# ce3.net
KiCad netlist of a schematic drawn in EAGLE
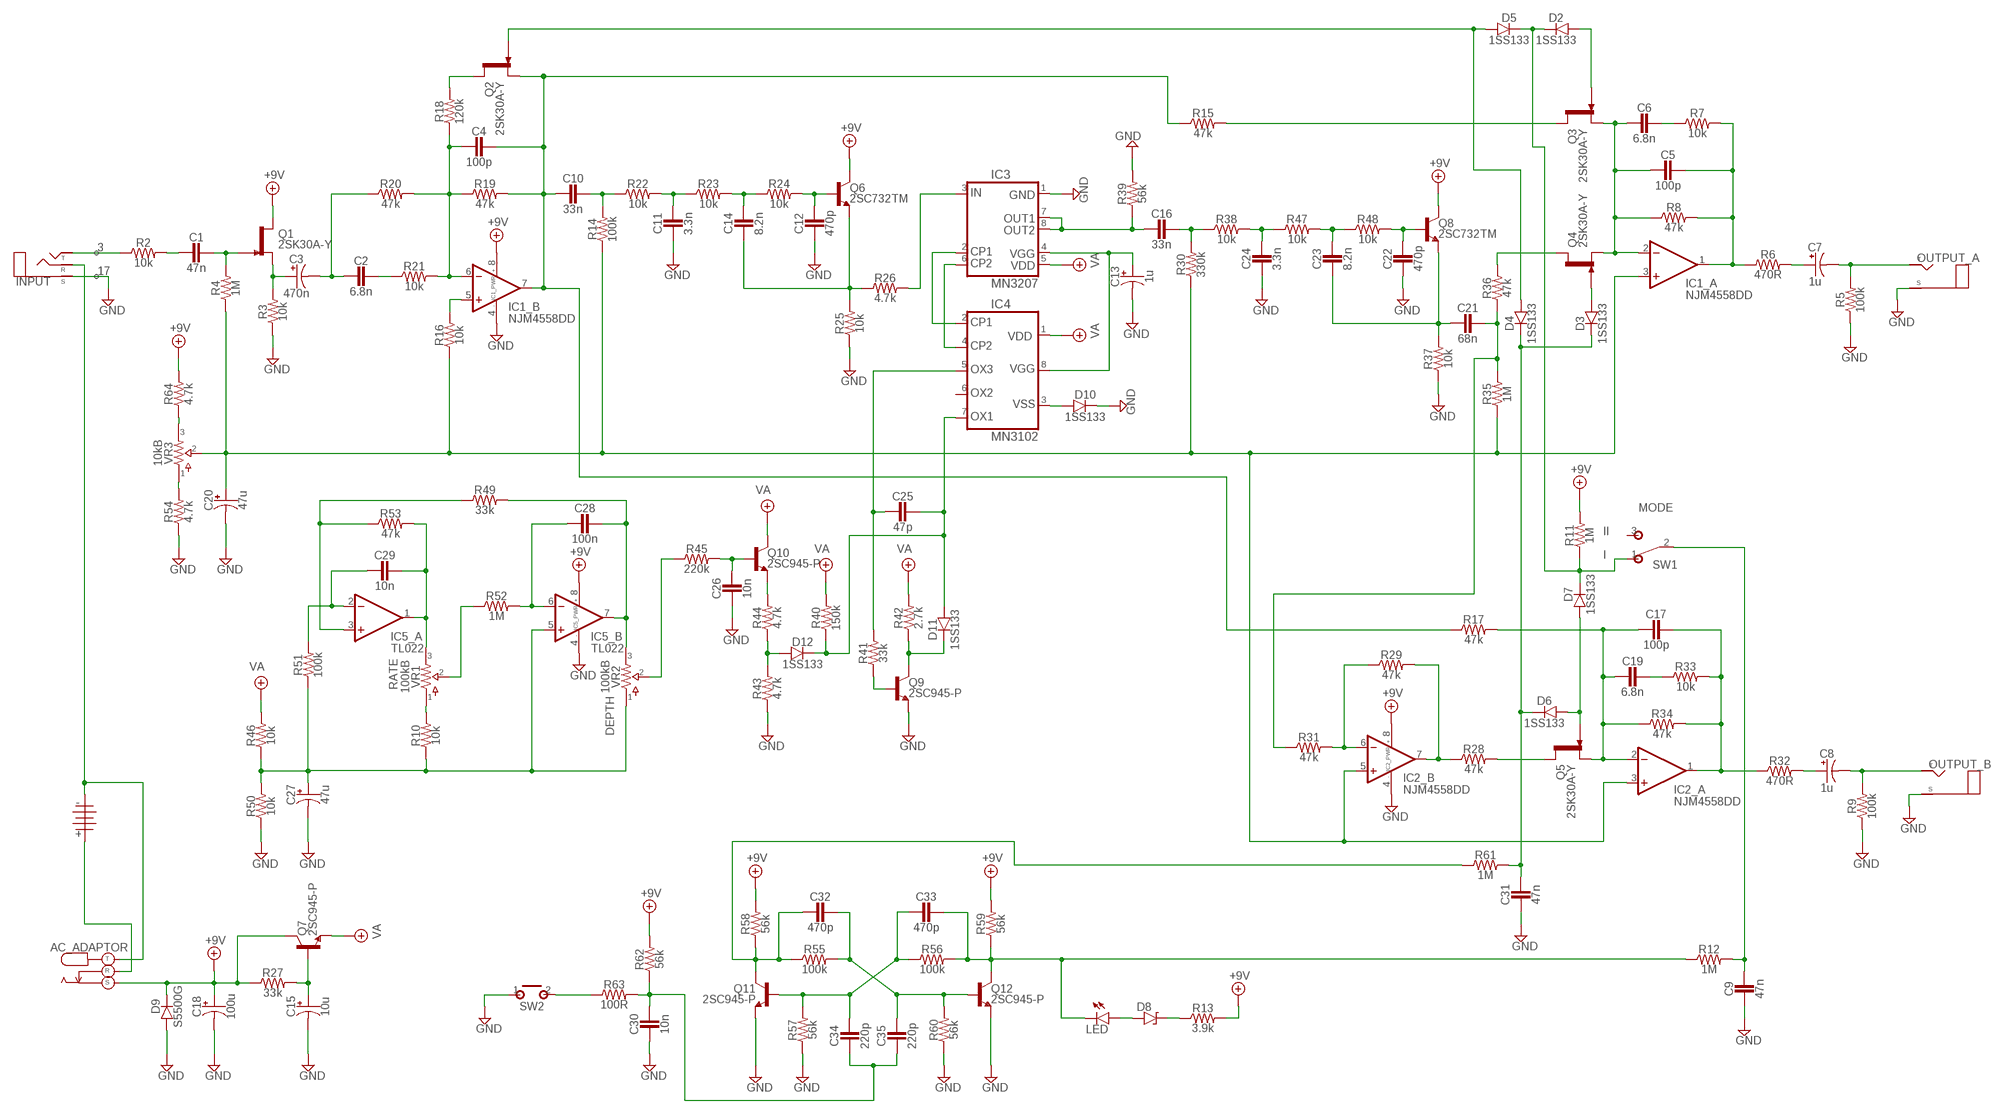
[diagram p0: schematic, sheet 1]

(export (version "E")
  (design (tool "Eeschema 10.0.6"))
  (components
    (comp (ref "1101")
      (value "BATTERY")
      (footprint "eagle-import:TWO_PADS")
      (libsource (lib "eagle-import") (part "BATTERY"))
    )
    (comp (ref "AC_ADAPTOR")
      (value "DC_KOBICONN")
      (footprint "eagle-import:DC_KOBICONN")
      (libsource (lib "eagle-import") (part "DC_KOBICONN"))
    )
    (comp (ref "C1")
      (value "47n")
      (footprint "eagle-import:BOX_SMALL")
      (libsource (lib "eagle-import") (part "CER/FILMBOX.1"))
    )
    (comp (ref "C2")
      (value "6.8n")
      (footprint "eagle-import:BOX_SMALL")
      (libsource (lib "eagle-import") (part "CER/FILMBOX.1"))
    )
    (comp (ref "C3")
      (value "470n")
      (footprint "eagle-import:040_020")
      (libsource (lib "eagle-import") (part "0400"))
    )
    (comp (ref "C4")
      (value "100p")
      (footprint "eagle-import:BOX_SMALL")
      (libsource (lib "eagle-import") (part "CER/FILMBOX.1"))
    )
    (comp (ref "C5")
      (value "100p")
      (footprint "eagle-import:BOX_SMALL")
      (libsource (lib "eagle-import") (part "CER/FILMBOX.1"))
    )
    (comp (ref "C6")
      (value "6.8n")
      (footprint "eagle-import:BOX_SMALL")
      (libsource (lib "eagle-import") (part "CER/FILMBOX.1"))
    )
    (comp (ref "C7")
      (value "1u")
      (footprint "eagle-import:040_020")
      (libsource (lib "eagle-import") (part "0400"))
    )
    (comp (ref "C8")
      (value "1u")
      (footprint "eagle-import:040_020")
      (libsource (lib "eagle-import") (part "0400"))
    )
    (comp (ref "C9")
      (value "47n")
      (footprint "eagle-import:BOX_SMALL")
      (libsource (lib "eagle-import") (part "CER/FILMBOX.1"))
    )
    (comp (ref "C10")
      (value "33n")
      (footprint "eagle-import:BOX_SMALL")
      (libsource (lib "eagle-import") (part "CER/FILMBOX.1"))
    )
    (comp (ref "C11")
      (value "3.3n")
      (footprint "eagle-import:BOX_SMALL")
      (libsource (lib "eagle-import") (part "CER/FILMBOX.1"))
    )
    (comp (ref "C12")
      (value "470p")
      (footprint "eagle-import:BOX_SMALL")
      (libsource (lib "eagle-import") (part "CER/FILMBOX.1"))
    )
    (comp (ref "C13")
      (value "1u")
      (footprint "eagle-import:040_020")
      (libsource (lib "eagle-import") (part "0400"))
    )
    (comp (ref "C14")
      (value "8.2n")
      (footprint "eagle-import:BOX_SMALL")
      (libsource (lib "eagle-import") (part "CER/FILMBOX.1"))
    )
    (comp (ref "C15")
      (value "10u")
      (footprint "eagle-import:040_020")
      (libsource (lib "eagle-import") (part "0400"))
    )
    (comp (ref "C16")
      (value "33n")
      (footprint "eagle-import:BOX_SMALL")
      (libsource (lib "eagle-import") (part "CER/FILMBOX.1"))
    )
    (comp (ref "C17")
      (value "100p")
      (footprint "eagle-import:BOX_SMALL")
      (libsource (lib "eagle-import") (part "CER/FILMBOX.1"))
    )
    (comp (ref "C18")
      (value "100u")
      (footprint "eagle-import:040_020")
      (libsource (lib "eagle-import") (part "0400"))
    )
    (comp (ref "C19")
      (value "6.8n")
      (footprint "eagle-import:BOX_SMALL")
      (libsource (lib "eagle-import") (part "CER/FILMBOX.1"))
    )
    (comp (ref "C20")
      (value "47u")
      (footprint "eagle-import:040_020")
      (libsource (lib "eagle-import") (part "0400"))
    )
    (comp (ref "C21")
      (value "68n")
      (footprint "eagle-import:BOX_SMALL")
      (libsource (lib "eagle-import") (part "CER/FILMBOX.1"))
    )
    (comp (ref "C22")
      (value "470p")
      (footprint "eagle-import:BOX_SMALL")
      (libsource (lib "eagle-import") (part "CER/FILMBOX.1"))
    )
    (comp (ref "C23")
      (value "8.2n")
      (footprint "eagle-import:BOX_SMALL")
      (libsource (lib "eagle-import") (part "CER/FILMBOX.1"))
    )
    (comp (ref "C24")
      (value "3.3n")
      (footprint "eagle-import:BOX_SMALL")
      (libsource (lib "eagle-import") (part "CER/FILMBOX.1"))
    )
    (comp (ref "C25")
      (value "47p")
      (footprint "eagle-import:BOX_SMALL")
      (libsource (lib "eagle-import") (part "CER/FILMBOX.1"))
    )
    (comp (ref "C26")
      (value "10n")
      (footprint "eagle-import:BOX_SMALL")
      (libsource (lib "eagle-import") (part "CER/FILMBOX.1"))
    )
    (comp (ref "C27")
      (value "47u")
      (footprint "eagle-import:040_020")
      (libsource (lib "eagle-import") (part "0400"))
    )
    (comp (ref "C28")
      (value "100n")
      (footprint "eagle-import:BOX_SMALL")
      (libsource (lib "eagle-import") (part "CER/FILMBOX.1"))
    )
    (comp (ref "C29")
      (value "10n")
      (footprint "eagle-import:BOX_SMALL")
      (libsource (lib "eagle-import") (part "CER/FILMBOX.1"))
    )
    (comp (ref "C30")
      (value "10n")
      (footprint "eagle-import:BOX_SMALL")
      (libsource (lib "eagle-import") (part "CER/FILMBOX.1"))
    )
    (comp (ref "C31")
      (value "47n")
      (footprint "eagle-import:BOX_SMALL")
      (libsource (lib "eagle-import") (part "CER/FILMBOX.1"))
    )
    (comp (ref "C32")
      (value "470p")
      (footprint "eagle-import:BOX_SMALL")
      (libsource (lib "eagle-import") (part "CER/FILMBOX.1"))
    )
    (comp (ref "C33")
      (value "470p")
      (footprint "eagle-import:BOX_SMALL")
      (libsource (lib "eagle-import") (part "CER/FILMBOX.1"))
    )
    (comp (ref "C34")
      (value "220p")
      (footprint "eagle-import:BOX_SMALL")
      (libsource (lib "eagle-import") (part "CER/FILMBOX.1"))
    )
    (comp (ref "C35")
      (value "220p")
      (footprint "eagle-import:BOX_SMALL")
      (libsource (lib "eagle-import") (part "CER/FILMBOX.1"))
    )
    (comp (ref "D2")
      (value "1SS133")
      (footprint "eagle-import:DO35-2")
      (libsource (lib "eagle-import") (part "DO35.2"))
    )
    (comp (ref "D3")
      (value "1SS133")
      (footprint "eagle-import:DO35-2")
      (libsource (lib "eagle-import") (part "DO35.2"))
    )
    (comp (ref "D4")
      (value "1SS133")
      (footprint "eagle-import:DO35-2")
      (libsource (lib "eagle-import") (part "DO35.2"))
    )
    (comp (ref "D5")
      (value "1SS133")
      (footprint "eagle-import:DO35-2")
      (libsource (lib "eagle-import") (part "DO35.2"))
    )
    (comp (ref "D6")
      (value "1SS133")
      (footprint "eagle-import:DO35-2")
      (libsource (lib "eagle-import") (part "DO35.2"))
    )
    (comp (ref "D7")
      (value "1SS133")
      (footprint "eagle-import:DO35-2")
      (libsource (lib "eagle-import") (part "DO35.2"))
    )
    (comp (ref "D8")
      (value "ZENER.2")
      (footprint "eagle-import:DO41-2")
      (libsource (lib "eagle-import") (part "ZENER.2"))
    )
    (comp (ref "D9")
      (value "S5500G")
      (footprint "eagle-import:DO35-2")
      (libsource (lib "eagle-import") (part "DO35.2"))
    )
    (comp (ref "D10")
      (value "1SS133")
      (footprint "eagle-import:DO35-2")
      (libsource (lib "eagle-import") (part "DO35.2"))
    )
    (comp (ref "D11")
      (value "1SS133")
      (footprint "eagle-import:DO35-2")
      (libsource (lib "eagle-import") (part "DO35.2"))
    )
    (comp (ref "D12")
      (value "1SS133")
      (footprint "eagle-import:DO35-2")
      (libsource (lib "eagle-import") (part "DO35.2"))
    )
    (comp (ref "IC1")
      (value "NJM4558DD")
      (footprint "eagle-import:DIL0")
      (libsource (lib "eagle-import") (part "DUALTH"))
    )
    (comp (ref "IC2")
      (value "NJM4558DD")
      (footprint "eagle-import:DIL0")
      (libsource (lib "eagle-import") (part "DUALTH"))
    )
    (comp (ref "IC3")
      (value "MN3207")
      (footprint "eagle-import:DIL0")
      (libsource (lib "eagle-import") (part "BL3208"))
    )
    (comp (ref "IC4")
      (value "MN3102")
      (footprint "eagle-import:DIL8")
      (libsource (lib "eagle-import") (part "CLOCK"))
    )
    (comp (ref "IC5")
      (value "TL022")
      (footprint "eagle-import:DIL0")
      (libsource (lib "eagle-import") (part "DUALTH"))
    )
    (comp (ref "INPUT")
      (value "STEREO3PADS")
      (footprint "eagle-import:THREEPADS")
      (libsource (lib "eagle-import") (part "STEREO3PADS"))
    )
    (comp (ref "LED")
      (value "LED")
      (footprint "eagle-import:3MM_D")
      (libsource (lib "eagle-import") (part "LED"))
    )
    (comp (ref "OUTPUT_A")
      (value "MONO")
      (footprint "eagle-import:TWO_PADS")
      (libsource (lib "eagle-import") (part "MONO"))
    )
    (comp (ref "OUTPUT_B")
      (value "MONO")
      (footprint "eagle-import:TWO_PADS")
      (libsource (lib "eagle-import") (part "MONO"))
    )
    (comp (ref "Q1")
      (value "2SK30A-Y")
      (footprint "eagle-import:TO92-")
      (libsource (lib "eagle-import") (part "2N5457"))
    )
    (comp (ref "Q2")
      (value "2SK30A-Y")
      (footprint "eagle-import:TO92-")
      (libsource (lib "eagle-import") (part "2N5457"))
    )
    (comp (ref "Q3")
      (value "2SK30A-Y")
      (footprint "eagle-import:TO92-")
      (libsource (lib "eagle-import") (part "2N5457"))
    )
    (comp (ref "Q4")
      (value "2SK30A-Y")
      (footprint "eagle-import:TO92-")
      (libsource (lib "eagle-import") (part "2N5457"))
    )
    (comp (ref "Q5")
      (value "2SK30A-Y")
      (footprint "eagle-import:TO92-")
      (libsource (lib "eagle-import") (part "2N5457"))
    )
    (comp (ref "Q6")
      (value "2SC732TM")
      (footprint "eagle-import:TO92-")
      (libsource (lib "eagle-import") (part "2SC828A"))
    )
    (comp (ref "Q7")
      (value "2SC945-P")
      (footprint "eagle-import:TO92-")
      (libsource (lib "eagle-import") (part "2SC828A"))
    )
    (comp (ref "Q8")
      (value "2SC732TM")
      (footprint "eagle-import:TO92-")
      (libsource (lib "eagle-import") (part "2SC828A"))
    )
    (comp (ref "Q9")
      (value "2SC945-P")
      (footprint "eagle-import:TO92-")
      (libsource (lib "eagle-import") (part "2SC828A"))
    )
    (comp (ref "Q10")
      (value "2SC945-P")
      (footprint "eagle-import:TO92-")
      (libsource (lib "eagle-import") (part "2SC828A"))
    )
    (comp (ref "Q11")
      (value "2SC945-P")
      (footprint "eagle-import:TO92-")
      (libsource (lib "eagle-import") (part "2SC828A"))
    )
    (comp (ref "Q12")
      (value "2SC945-P")
      (footprint "eagle-import:TO92-")
      (libsource (lib "eagle-import") (part "2SC828A"))
    )
    (comp (ref "R2")
      (value "10k")
      (footprint "eagle-import:R0207_3")
      (libsource (lib "eagle-import") (part "R_.3B"))
    )
    (comp (ref "R3")
      (value "10k")
      (footprint "eagle-import:R0207_3")
      (libsource (lib "eagle-import") (part "R_.3B"))
    )
    (comp (ref "R4")
      (value "1M")
      (footprint "eagle-import:R0207_3")
      (libsource (lib "eagle-import") (part "R_.3B"))
    )
    (comp (ref "R5")
      (value "100k")
      (footprint "eagle-import:R0207_3")
      (libsource (lib "eagle-import") (part "R_.3B"))
    )
    (comp (ref "R6")
      (value "470R")
      (footprint "eagle-import:R0207_3")
      (libsource (lib "eagle-import") (part "R_.3B"))
    )
    (comp (ref "R7")
      (value "10k")
      (footprint "eagle-import:R0207_3")
      (libsource (lib "eagle-import") (part "R_.3B"))
    )
    (comp (ref "R8")
      (value "47k")
      (footprint "eagle-import:R0207_3")
      (libsource (lib "eagle-import") (part "R_.3B"))
    )
    (comp (ref "R9")
      (value "100k")
      (footprint "eagle-import:R0207_3")
      (libsource (lib "eagle-import") (part "R_.3B"))
    )
    (comp (ref "R10")
      (value "10k")
      (footprint "eagle-import:R0207_3")
      (libsource (lib "eagle-import") (part "R_.3B"))
    )
    (comp (ref "R11")
      (value "1M")
      (footprint "eagle-import:R0207_3")
      (libsource (lib "eagle-import") (part "R_.3B"))
    )
    (comp (ref "R12")
      (value "1M")
      (footprint "eagle-import:R0207_3")
      (libsource (lib "eagle-import") (part "R_.3B"))
    )
    (comp (ref "R13")
      (value "3.9k")
      (footprint "eagle-import:R0207_3")
      (libsource (lib "eagle-import") (part "R_.3B"))
    )
    (comp (ref "R14")
      (value "100k")
      (footprint "eagle-import:R0207_3")
      (libsource (lib "eagle-import") (part "R_.3B"))
    )
    (comp (ref "R15")
      (value "47k")
      (footprint "eagle-import:R0207_3")
      (libsource (lib "eagle-import") (part "R_.3B"))
    )
    (comp (ref "R16")
      (value "10k")
      (footprint "eagle-import:R0207_3")
      (libsource (lib "eagle-import") (part "R_.3B"))
    )
    (comp (ref "R17")
      (value "47k")
      (footprint "eagle-import:R0207_3")
      (libsource (lib "eagle-import") (part "R_.3B"))
    )
    (comp (ref "R18")
      (value "120k")
      (footprint "eagle-import:R0207_3")
      (libsource (lib "eagle-import") (part "R_.3B"))
    )
    (comp (ref "R19")
      (value "47k")
      (footprint "eagle-import:R0207_3")
      (libsource (lib "eagle-import") (part "R_.3B"))
    )
    (comp (ref "R20")
      (value "47k")
      (footprint "eagle-import:R0207_3")
      (libsource (lib "eagle-import") (part "R_.3B"))
    )
    (comp (ref "R21")
      (value "10k")
      (footprint "eagle-import:R0207_3")
      (libsource (lib "eagle-import") (part "R_.3B"))
    )
    (comp (ref "R22")
      (value "10k")
      (footprint "eagle-import:R0207_3")
      (libsource (lib "eagle-import") (part "R_.3B"))
    )
    (comp (ref "R23")
      (value "10k")
      (footprint "eagle-import:R0207_3")
      (libsource (lib "eagle-import") (part "R_.3B"))
    )
    (comp (ref "R24")
      (value "10k")
      (footprint "eagle-import:R0207_3")
      (libsource (lib "eagle-import") (part "R_.3B"))
    )
    (comp (ref "R25")
      (value "10k")
      (footprint "eagle-import:R0207_3")
      (libsource (lib "eagle-import") (part "R_.3B"))
    )
    (comp (ref "R26")
      (value "4.7k")
      (footprint "eagle-import:R0207_3")
      (libsource (lib "eagle-import") (part "R_.3B"))
    )
    (comp (ref "R27")
      (value "33k")
      (footprint "eagle-import:R0207_3")
      (libsource (lib "eagle-import") (part "R_.3B"))
    )
    (comp (ref "R28")
      (value "47k")
      (footprint "eagle-import:R0207_3")
      (libsource (lib "eagle-import") (part "R_.3B"))
    )
    (comp (ref "R29")
      (value "47k")
      (footprint "eagle-import:R0207_3")
      (libsource (lib "eagle-import") (part "R_.3B"))
    )
    (comp (ref "R30")
      (value "330k")
      (footprint "eagle-import:R0207_3")
      (libsource (lib "eagle-import") (part "R_.3B"))
    )
    (comp (ref "R31")
      (value "47k")
      (footprint "eagle-import:R0207_3")
      (libsource (lib "eagle-import") (part "R_.3B"))
    )
    (comp (ref "R32")
      (value "470R")
      (footprint "eagle-import:R0207_3")
      (libsource (lib "eagle-import") (part "R_.3B"))
    )
    (comp (ref "R33")
      (value "10k")
      (footprint "eagle-import:R0207_3")
      (libsource (lib "eagle-import") (part "R_.3B"))
    )
    (comp (ref "R34")
      (value "47k")
      (footprint "eagle-import:R0207_3")
      (libsource (lib "eagle-import") (part "R_.3B"))
    )
    (comp (ref "R35")
      (value "1M")
      (footprint "eagle-import:R0207_3")
      (libsource (lib "eagle-import") (part "R_.3B"))
    )
    (comp (ref "R36")
      (value "47k")
      (footprint "eagle-import:R0207_3")
      (libsource (lib "eagle-import") (part "R_.3B"))
    )
    (comp (ref "R37")
      (value "10k")
      (footprint "eagle-import:R0207_3")
      (libsource (lib "eagle-import") (part "R_.3B"))
    )
    (comp (ref "R38")
      (value "10k")
      (footprint "eagle-import:R0207_3")
      (libsource (lib "eagle-import") (part "R_.3B"))
    )
    (comp (ref "R39")
      (value "56k")
      (footprint "eagle-import:R0207_3")
      (libsource (lib "eagle-import") (part "R_.3B"))
    )
    (comp (ref "R40")
      (value "150k")
      (footprint "eagle-import:R0207_3")
      (libsource (lib "eagle-import") (part "R_.3B"))
    )
    (comp (ref "R41")
      (value "33k")
      (footprint "eagle-import:R0207_3")
      (libsource (lib "eagle-import") (part "R_.3B"))
    )
    (comp (ref "R42")
      (value "2.7k")
      (footprint "eagle-import:R0207_3")
      (libsource (lib "eagle-import") (part "R_.3B"))
    )
    (comp (ref "R43")
      (value "4.7k")
      (footprint "eagle-import:R0207_3")
      (libsource (lib "eagle-import") (part "R_.3B"))
    )
    (comp (ref "R44")
      (value "4.7k")
      (footprint "eagle-import:R0207_3")
      (libsource (lib "eagle-import") (part "R_.3B"))
    )
    (comp (ref "R45")
      (value "220k")
      (footprint "eagle-import:R0207_3")
      (libsource (lib "eagle-import") (part "R_.3B"))
    )
    (comp (ref "R46")
      (value "10k")
      (footprint "eagle-import:R0207_3")
      (libsource (lib "eagle-import") (part "R_.3B"))
    )
    (comp (ref "R47")
      (value "10k")
      (footprint "eagle-import:R0207_3")
      (libsource (lib "eagle-import") (part "R_.3B"))
    )
    (comp (ref "R48")
      (value "10k")
      (footprint "eagle-import:R0207_3")
      (libsource (lib "eagle-import") (part "R_.3B"))
    )
    (comp (ref "R49")
      (value "33k")
      (footprint "eagle-import:R0207_3")
      (libsource (lib "eagle-import") (part "R_.3B"))
    )
    (comp (ref "R50")
      (value "10k")
      (footprint "eagle-import:R0207_3")
      (libsource (lib "eagle-import") (part "R_.3B"))
    )
    (comp (ref "R51")
      (value "100k")
      (footprint "eagle-import:R0207_3")
      (libsource (lib "eagle-import") (part "R_.3B"))
    )
    (comp (ref "R52")
      (value "1M")
      (footprint "eagle-import:R0207_3")
      (libsource (lib "eagle-import") (part "R_.3B"))
    )
    (comp (ref "R53")
      (value "47k")
      (footprint "eagle-import:R0207_3")
      (libsource (lib "eagle-import") (part "R_.3B"))
    )
    (comp (ref "R54")
      (value "4.7k")
      (footprint "eagle-import:R0207_3")
      (libsource (lib "eagle-import") (part "R_.3B"))
    )
    (comp (ref "R55")
      (value "100k")
      (footprint "eagle-import:R0207_3")
      (libsource (lib "eagle-import") (part "R_.3B"))
    )
    (comp (ref "R56")
      (value "100k")
      (footprint "eagle-import:R0207_3")
      (libsource (lib "eagle-import") (part "R_.3B"))
    )
    (comp (ref "R57")
      (value "56k")
      (footprint "eagle-import:R0207_3")
      (libsource (lib "eagle-import") (part "R_.3B"))
    )
    (comp (ref "R58")
      (value "56k")
      (footprint "eagle-import:R0207_3")
      (libsource (lib "eagle-import") (part "R_.3B"))
    )
    (comp (ref "R59")
      (value "56k")
      (footprint "eagle-import:R0207_3")
      (libsource (lib "eagle-import") (part "R_.3B"))
    )
    (comp (ref "R60")
      (value "56k")
      (footprint "eagle-import:R0207_3")
      (libsource (lib "eagle-import") (part "R_.3B"))
    )
    (comp (ref "R61")
      (value "1M")
      (footprint "eagle-import:R0207_3")
      (libsource (lib "eagle-import") (part "R_.3B"))
    )
    (comp (ref "R62")
      (value "56k")
      (footprint "eagle-import:R0207_3")
      (libsource (lib "eagle-import") (part "R_.3B"))
    )
    (comp (ref "R63")
      (value "100R")
      (footprint "eagle-import:R0207_3")
      (libsource (lib "eagle-import") (part "R_.3B"))
    )
    (comp (ref "R64")
      (value "4.7k")
      (footprint "eagle-import:R0207_3")
      (libsource (lib "eagle-import") (part "R_.3B"))
    )
    (comp (ref "SW1")
      (value "SPDT")
      (footprint "eagle-import:M9040P")
      (libsource (lib "eagle-import") (part "SPDT"))
    )
    (comp (ref "SW2")
      (value "MOMENTARY")
      (footprint "eagle-import:SPST")
      (libsource (lib "eagle-import") (part "MOMENTARY"))
    )
    (comp (ref "VR1")
      (value "100kB")
      (footprint "eagle-import:16MM")
      (libsource (lib "eagle-import") (part "POTS16MM"))
    )
    (comp (ref "VR2")
      (value "100kB")
      (footprint "eagle-import:16MM")
      (libsource (lib "eagle-import") (part "POTS16MM"))
    )
    (comp (ref "VR3")
      (value "10kB")
      (footprint "eagle-import:16MM")
      (libsource (lib "eagle-import") (part "POTS16MM"))
    )
  )
  (nets
    (net (code "1") (name "+9V") (class "Default")
      (node (ref "AC_ADAPTOR") (pin "S") (pinfunction "S_S") (pintype "bidirectional"))
      (node (ref "C18") (pin "+") (pinfunction "+_+") (pintype "passive"))
      (node (ref "D9") (pin "C") (pinfunction "C_C") (pintype "passive"))
      (node (ref "IC1") (pin "8") (pinfunction "V+_8") (pintype "power_in"))
      (node (ref "IC2") (pin "8") (pinfunction "V+_8") (pintype "power_in"))
      (node (ref "IC5") (pin "8") (pinfunction "V+_8") (pintype "power_in"))
      (node (ref "Q1") (pin "3") (pinfunction "D_3") (pintype "passive"))
      (node (ref "Q6") (pin "2") (pinfunction "C_2") (pintype "passive"))
      (node (ref "Q7") (pin "2") (pinfunction "C_2") (pintype "passive"))
      (node (ref "Q8") (pin "2") (pinfunction "C_2") (pintype "passive"))
      (node (ref "R11") (pin "2") (pinfunction "2_2") (pintype "passive"))
      (node (ref "R13") (pin "2") (pinfunction "2_2") (pintype "passive"))
      (node (ref "R27") (pin "1") (pinfunction "1_1") (pintype "passive"))
      (node (ref "R58") (pin "2") (pinfunction "2_2") (pintype "passive"))
      (node (ref "R59") (pin "2") (pinfunction "2_2") (pintype "passive"))
      (node (ref "R62") (pin "2") (pinfunction "2_2") (pintype "passive"))
      (node (ref "R64") (pin "2") (pinfunction "2_2") (pintype "passive"))
    )
    (net (code "2") (name "GND") (class "Default")
      (node (ref "C11") (pin "2") (pinfunction "2_2") (pintype "passive"))
      (node (ref "C12") (pin "2") (pinfunction "2_2") (pintype "passive"))
      (node (ref "C13") (pin "-") (pinfunction "-_-") (pintype "passive"))
      (node (ref "C15") (pin "-") (pinfunction "-_-") (pintype "passive"))
      (node (ref "C18") (pin "-") (pinfunction "-_-") (pintype "passive"))
      (node (ref "C20") (pin "-") (pinfunction "-_-") (pintype "passive"))
      (node (ref "C22") (pin "2") (pinfunction "2_2") (pintype "passive"))
      (node (ref "C24") (pin "2") (pinfunction "2_2") (pintype "passive"))
      (node (ref "C26") (pin "2") (pinfunction "2_2") (pintype "passive"))
      (node (ref "C27") (pin "-") (pinfunction "-_-") (pintype "passive"))
      (node (ref "C30") (pin "2") (pinfunction "2_2") (pintype "passive"))
      (node (ref "C31") (pin "2") (pinfunction "2_2") (pintype "passive"))
      (node (ref "C9") (pin "2") (pinfunction "2_2") (pintype "passive"))
      (node (ref "D10") (pin "C") (pinfunction "C_C") (pintype "passive"))
      (node (ref "D9") (pin "A") (pinfunction "A_A") (pintype "passive"))
      (node (ref "IC1") (pin "4") (pinfunction "V-_4") (pintype "power_in"))
      (node (ref "IC2") (pin "4") (pinfunction "V-_4") (pintype "power_in"))
      (node (ref "IC3") (pin "1") (pinfunction "1_1") (pintype "bidirectional"))
      (node (ref "IC5") (pin "4") (pinfunction "V-_4") (pintype "power_in"))
      (node (ref "INPUT") (pin "SLEEVE") (pinfunction "S_SLEEVE") (pintype "passive"))
      (node (ref "OUTPUT_A") (pin "S") (pinfunction "SLEEVE_S") (pintype "passive"))
      (node (ref "OUTPUT_B") (pin "S") (pinfunction "SLEEVE_S") (pintype "passive"))
      (node (ref "Q11") (pin "3") (pinfunction "E_3") (pintype "passive"))
      (node (ref "Q12") (pin "3") (pinfunction "E_3") (pintype "passive"))
      (node (ref "Q9") (pin "3") (pinfunction "E_3") (pintype "passive"))
      (node (ref "R25") (pin "1") (pinfunction "1_1") (pintype "passive"))
      (node (ref "R3") (pin "1") (pinfunction "1_1") (pintype "passive"))
      (node (ref "R37") (pin "1") (pinfunction "1_1") (pintype "passive"))
      (node (ref "R39") (pin "2") (pinfunction "2_2") (pintype "passive"))
      (node (ref "R43") (pin "1") (pinfunction "1_1") (pintype "passive"))
      (node (ref "R5") (pin "1") (pinfunction "1_1") (pintype "passive"))
      (node (ref "R50") (pin "1") (pinfunction "1_1") (pintype "passive"))
      (node (ref "R54") (pin "1") (pinfunction "1_1") (pintype "passive"))
      (node (ref "R57") (pin "1") (pinfunction "1_1") (pintype "passive"))
      (node (ref "R60") (pin "1") (pinfunction "1_1") (pintype "passive"))
      (node (ref "R9") (pin "1") (pinfunction "1_1") (pintype "passive"))
      (node (ref "SW2") (pin "1") (pinfunction "P_1") (pintype "passive"))
    )
    (net (code "3") (name "Net-(1101-P$1)") (class "Default")
      (node (ref "1101") (pin "T") (pinfunction "P$1_T") (pintype "bidirectional"))
      (node (ref "AC_ADAPTOR") (pin "R") (pinfunction "R_R") (pintype "bidirectional"))
    )
    (net (code "4") (name "Net-(1101-P$2)") (class "Default")
      (node (ref "1101") (pin "S") (pinfunction "P$2_S") (pintype "bidirectional"))
      (node (ref "AC_ADAPTOR") (pin "T") (pinfunction "T_T") (pintype "bidirectional"))
      (node (ref "INPUT") (pin "RING") (pinfunction "R_RING") (pintype "passive"))
    )
    (net (code "5") (name "Net-(C1-Pad2)") (class "Default")
      (node (ref "C1") (pin "2") (pinfunction "2_2") (pintype "passive"))
      (node (ref "R2") (pin "2") (pinfunction "2_2") (pintype "passive"))
    )
    (net (code "6") (name "Net-(C2-Pad1)") (class "Default")
      (node (ref "C2") (pin "1") (pinfunction "1_1") (pintype "passive"))
      (node (ref "R21") (pin "1") (pinfunction "1_1") (pintype "passive"))
    )
    (net (code "7") (name "Net-(C2-Pad2)") (class "Default")
      (node (ref "C2") (pin "2") (pinfunction "2_2") (pintype "passive"))
      (node (ref "C3") (pin "-") (pinfunction "-_-") (pintype "passive"))
      (node (ref "R20") (pin "1") (pinfunction "1_1") (pintype "passive"))
    )
    (net (code "8") (name "Net-(C6-Pad1)") (class "Default")
      (node (ref "C6") (pin "1") (pinfunction "1_1") (pintype "passive"))
      (node (ref "R7") (pin "1") (pinfunction "1_1") (pintype "passive"))
    )
    (net (code "9") (name "Net-(C7-Pad+)") (class "Default")
      (node (ref "C7") (pin "+") (pinfunction "+_+") (pintype "passive"))
      (node (ref "R6") (pin "2") (pinfunction "2_2") (pintype "passive"))
    )
    (net (code "10") (name "Net-(C8-Pad+)") (class "Default")
      (node (ref "C8") (pin "+") (pinfunction "+_+") (pintype "passive"))
      (node (ref "R32") (pin "2") (pinfunction "2_2") (pintype "passive"))
    )
    (net (code "11") (name "Net-(C10-Pad1)") (class "Default")
      (node (ref "C10") (pin "1") (pinfunction "1_1") (pintype "passive"))
      (node (ref "R14") (pin "2") (pinfunction "2_2") (pintype "passive"))
      (node (ref "R22") (pin "1") (pinfunction "1_1") (pintype "passive"))
    )
    (net (code "12") (name "Net-(C11-Pad1)") (class "Default")
      (node (ref "C11") (pin "1") (pinfunction "1_1") (pintype "passive"))
      (node (ref "R22") (pin "2") (pinfunction "2_2") (pintype "passive"))
      (node (ref "R23") (pin "1") (pinfunction "1_1") (pintype "passive"))
    )
    (net (code "13") (name "Net-(C14-Pad1)") (class "Default")
      (node (ref "C14") (pin "1") (pinfunction "1_1") (pintype "passive"))
      (node (ref "R23") (pin "2") (pinfunction "2_2") (pintype "passive"))
      (node (ref "R24") (pin "1") (pinfunction "1_1") (pintype "passive"))
    )
    (net (code "14") (name "Net-(C16-Pad1)") (class "Default")
      (node (ref "C16") (pin "1") (pinfunction "1_1") (pintype "passive"))
      (node (ref "R30") (pin "2") (pinfunction "2_2") (pintype "passive"))
      (node (ref "R38") (pin "1") (pinfunction "1_1") (pintype "passive"))
    )
    (net (code "15") (name "Net-(C16-Pad2)") (class "Default")
      (node (ref "C16") (pin "2") (pinfunction "2_2") (pintype "passive"))
      (node (ref "IC3") (pin "7") (pinfunction "7_7") (pintype "bidirectional"))
      (node (ref "IC3") (pin "8") (pinfunction "8_8") (pintype "bidirectional"))
      (node (ref "R39") (pin "1") (pinfunction "1_1") (pintype "passive"))
    )
    (net (code "16") (name "Net-(C19-Pad1)") (class "Default")
      (node (ref "C19") (pin "1") (pinfunction "1_1") (pintype "passive"))
      (node (ref "R33") (pin "1") (pinfunction "1_1") (pintype "passive"))
    )
    (net (code "17") (name "Net-(C21-Pad1)") (class "Default")
      (node (ref "C21") (pin "1") (pinfunction "1_1") (pintype "passive"))
      (node (ref "R31") (pin "1") (pinfunction "1_1") (pintype "passive"))
      (node (ref "R35") (pin "2") (pinfunction "2_2") (pintype "passive"))
      (node (ref "R36") (pin "1") (pinfunction "1_1") (pintype "passive"))
    )
    (net (code "18") (name "Net-(C23-Pad1)") (class "Default")
      (node (ref "C23") (pin "1") (pinfunction "1_1") (pintype "passive"))
      (node (ref "R47") (pin "2") (pinfunction "2_2") (pintype "passive"))
      (node (ref "R48") (pin "1") (pinfunction "1_1") (pintype "passive"))
    )
    (net (code "19") (name "Net-(C24-Pad1)") (class "Default")
      (node (ref "C24") (pin "1") (pinfunction "1_1") (pintype "passive"))
      (node (ref "R38") (pin "2") (pinfunction "2_2") (pintype "passive"))
      (node (ref "R47") (pin "1") (pinfunction "1_1") (pintype "passive"))
    )
    (net (code "20") (name "Net-(C30-Pad1)") (class "Default")
      (node (ref "C30") (pin "1") (pinfunction "1_1") (pintype "passive"))
      (node (ref "C34") (pin "2") (pinfunction "2_2") (pintype "passive"))
      (node (ref "C35") (pin "2") (pinfunction "2_2") (pintype "passive"))
      (node (ref "R62") (pin "1") (pinfunction "1_1") (pintype "passive"))
      (node (ref "R63") (pin "2") (pinfunction "2_2") (pintype "passive"))
    )
    (net (code "21") (name "Net-(C31-Pad1)") (class "Default")
      (node (ref "C31") (pin "1") (pinfunction "1_1") (pintype "passive"))
      (node (ref "D3") (pin "C") (pinfunction "C_C") (pintype "passive"))
      (node (ref "D4") (pin "C") (pinfunction "C_C") (pintype "passive"))
      (node (ref "D6") (pin "C") (pinfunction "C_C") (pintype "passive"))
      (node (ref "R61") (pin "2") (pinfunction "2_2") (pintype "passive"))
    )
    (net (code "22") (name "Net-(D8-PadC)") (class "Default")
      (node (ref "D8") (pin "C") (pinfunction "C_C") (pintype "passive"))
      (node (ref "R13") (pin "1") (pinfunction "1_1") (pintype "passive"))
    )
    (net (code "23") (name "Net-(D12-PadA)") (class "Default")
      (node (ref "D12") (pin "A") (pinfunction "A_A") (pintype "passive"))
      (node (ref "R43") (pin "2") (pinfunction "2_2") (pintype "passive"))
      (node (ref "R44") (pin "1") (pinfunction "1_1") (pintype "passive"))
    )
    (net (code "24") (name "Net-(IC1A-+IN)") (class "Default")
      (node (ref "C20") (pin "+") (pinfunction "+_+") (pintype "passive"))
      (node (ref "IC1") (pin "3") (pinfunction "+IN_3") (pintype "input"))
      (node (ref "IC2") (pin "3") (pinfunction "+IN_3") (pintype "input"))
      (node (ref "IC2") (pin "5") (pinfunction "+IN_5") (pintype "input"))
      (node (ref "R14") (pin "1") (pinfunction "1_1") (pintype "passive"))
      (node (ref "R16") (pin "1") (pinfunction "1_1") (pintype "passive"))
      (node (ref "R30") (pin "1") (pinfunction "1_1") (pintype "passive"))
      (node (ref "R35") (pin "1") (pinfunction "1_1") (pintype "passive"))
      (node (ref "R4") (pin "1") (pinfunction "1_1") (pintype "passive"))
      (node (ref "VR3") (pin "2") (pinfunction "2_2") (pintype "passive"))
    )
    (net (code "25") (name "Net-(IC1A--IN)") (class "Default")
      (node (ref "C5") (pin "2") (pinfunction "2_2") (pintype "passive"))
      (node (ref "C6") (pin "2") (pinfunction "2_2") (pintype "passive"))
      (node (ref "IC1") (pin "2") (pinfunction "-IN_2") (pintype "input"))
      (node (ref "Q3") (pin "2") (pinfunction "S_2") (pintype "passive"))
      (node (ref "Q4") (pin "2") (pinfunction "S_2") (pintype "passive"))
      (node (ref "R8") (pin "1") (pinfunction "1_1") (pintype "passive"))
    )
    (net (code "26") (name "Net-(IC1A-OUT)") (class "Default")
      (node (ref "C5") (pin "1") (pinfunction "1_1") (pintype "passive"))
      (node (ref "IC1") (pin "1") (pinfunction "OUT_1") (pintype "output"))
      (node (ref "R6") (pin "1") (pinfunction "1_1") (pintype "passive"))
      (node (ref "R7") (pin "2") (pinfunction "2_2") (pintype "passive"))
      (node (ref "R8") (pin "2") (pinfunction "2_2") (pintype "passive"))
    )
    (net (code "27") (name "Net-(IC1B-+IN)") (class "Default")
      (node (ref "IC1") (pin "5") (pinfunction "+IN_5") (pintype "input"))
      (node (ref "R16") (pin "2") (pinfunction "2_2") (pintype "passive"))
    )
    (net (code "28") (name "Net-(IC1B--IN)") (class "Default")
      (node (ref "C4") (pin "2") (pinfunction "2_2") (pintype "passive"))
      (node (ref "IC1") (pin "6") (pinfunction "-IN_6") (pintype "input"))
      (node (ref "R18") (pin "1") (pinfunction "1_1") (pintype "passive"))
      (node (ref "R19") (pin "1") (pinfunction "1_1") (pintype "passive"))
      (node (ref "R20") (pin "2") (pinfunction "2_2") (pintype "passive"))
      (node (ref "R21") (pin "2") (pinfunction "2_2") (pintype "passive"))
    )
    (net (code "29") (name "Net-(IC1B-OUT)") (class "Default")
      (node (ref "C10") (pin "2") (pinfunction "2_2") (pintype "passive"))
      (node (ref "C4") (pin "1") (pinfunction "1_1") (pintype "passive"))
      (node (ref "IC1") (pin "7") (pinfunction "OUT_7") (pintype "output"))
      (node (ref "Q2") (pin "2") (pinfunction "S_2") (pintype "passive"))
      (node (ref "R15") (pin "1") (pinfunction "1_1") (pintype "passive"))
      (node (ref "R17") (pin "1") (pinfunction "1_1") (pintype "passive"))
      (node (ref "R19") (pin "2") (pinfunction "2_2") (pintype "passive"))
    )
    (net (code "30") (name "Net-(IC2A--IN)") (class "Default")
      (node (ref "C17") (pin "2") (pinfunction "2_2") (pintype "passive"))
      (node (ref "C19") (pin "2") (pinfunction "2_2") (pintype "passive"))
      (node (ref "IC2") (pin "2") (pinfunction "-IN_2") (pintype "input"))
      (node (ref "Q5") (pin "2") (pinfunction "S_2") (pintype "passive"))
      (node (ref "R17") (pin "2") (pinfunction "2_2") (pintype "passive"))
      (node (ref "R34") (pin "1") (pinfunction "1_1") (pintype "passive"))
    )
    (net (code "31") (name "Net-(IC2A-OUT)") (class "Default")
      (node (ref "C17") (pin "1") (pinfunction "1_1") (pintype "passive"))
      (node (ref "IC2") (pin "1") (pinfunction "OUT_1") (pintype "output"))
      (node (ref "R32") (pin "1") (pinfunction "1_1") (pintype "passive"))
      (node (ref "R33") (pin "2") (pinfunction "2_2") (pintype "passive"))
      (node (ref "R34") (pin "2") (pinfunction "2_2") (pintype "passive"))
    )
    (net (code "32") (name "Net-(IC2B--IN)") (class "Default")
      (node (ref "IC2") (pin "6") (pinfunction "-IN_6") (pintype "input"))
      (node (ref "R29") (pin "1") (pinfunction "1_1") (pintype "passive"))
      (node (ref "R31") (pin "2") (pinfunction "2_2") (pintype "passive"))
    )
    (net (code "33") (name "Net-(IC2B-OUT)") (class "Default")
      (node (ref "IC2") (pin "7") (pinfunction "OUT_7") (pintype "output"))
      (node (ref "R28") (pin "1") (pinfunction "1_1") (pintype "passive"))
      (node (ref "R29") (pin "2") (pinfunction "2_2") (pintype "passive"))
    )
    (net (code "34") (name "Net-(IC3-Pad3)") (class "Default")
      (node (ref "IC3") (pin "3") (pinfunction "3_3") (pintype "bidirectional"))
      (node (ref "R26") (pin "2") (pinfunction "2_2") (pintype "passive"))
    )
    (net (code "35") (name "Net-(IC4-P$2)") (class "Default")
      (node (ref "IC3") (pin "2") (pinfunction "2_2") (pintype "bidirectional"))
      (node (ref "IC4") (pin "2") (pinfunction "P$2_2") (pintype "bidirectional"))
    )
    (net (code "36") (name "Net-(IC4-P$3)") (class "Default")
      (node (ref "D10") (pin "A") (pinfunction "A_A") (pintype "passive"))
      (node (ref "IC4") (pin "3") (pinfunction "P$3_3") (pintype "bidirectional"))
    )
    (net (code "37") (name "Net-(IC4-P$4)") (class "Default")
      (node (ref "IC3") (pin "6") (pinfunction "6_6") (pintype "bidirectional"))
      (node (ref "IC4") (pin "4") (pinfunction "P$4_4") (pintype "bidirectional"))
    )
    (net (code "38") (name "Net-(IC4-P$5)") (class "Default")
      (node (ref "C25") (pin "2") (pinfunction "2_2") (pintype "passive"))
      (node (ref "IC4") (pin "5") (pinfunction "P$5_5") (pintype "bidirectional"))
      (node (ref "R41") (pin "2") (pinfunction "2_2") (pintype "passive"))
    )
    (net (code "39") (name "Net-(IC4-P$7)") (class "Default")
      (node (ref "C25") (pin "1") (pinfunction "1_1") (pintype "passive"))
      (node (ref "D11") (pin "A") (pinfunction "A_A") (pintype "passive"))
      (node (ref "D12") (pin "C") (pinfunction "C_C") (pintype "passive"))
      (node (ref "IC4") (pin "7") (pinfunction "P$7_7") (pintype "bidirectional"))
      (node (ref "R40") (pin "1") (pinfunction "1_1") (pintype "passive"))
    )
    (net (code "40") (name "Net-(IC4-P$8)") (class "Default")
      (node (ref "C13") (pin "+") (pinfunction "+_+") (pintype "passive"))
      (node (ref "IC3") (pin "4") (pinfunction "4_4") (pintype "bidirectional"))
      (node (ref "IC4") (pin "8") (pinfunction "P$8_8") (pintype "bidirectional"))
    )
    (net (code "41") (name "Net-(IC5A-+IN)") (class "Default")
      (node (ref "IC5") (pin "3") (pinfunction "+IN_3") (pintype "input"))
      (node (ref "R49") (pin "1") (pinfunction "1_1") (pintype "passive"))
      (node (ref "R53") (pin "1") (pinfunction "1_1") (pintype "passive"))
    )
    (net (code "42") (name "Net-(IC5A--IN)") (class "Default")
      (node (ref "C29") (pin "2") (pinfunction "2_2") (pintype "passive"))
      (node (ref "IC5") (pin "2") (pinfunction "-IN_2") (pintype "input"))
      (node (ref "R51") (pin "2") (pinfunction "2_2") (pintype "passive"))
    )
    (net (code "43") (name "Net-(IC5A-OUT)") (class "Default")
      (node (ref "C29") (pin "1") (pinfunction "1_1") (pintype "passive"))
      (node (ref "IC5") (pin "1") (pinfunction "OUT_1") (pintype "output"))
      (node (ref "R53") (pin "2") (pinfunction "2_2") (pintype "passive"))
      (node (ref "VR1") (pin "3") (pinfunction "3_3") (pintype "passive"))
    )
    (net (code "44") (name "Net-(IC5B-+IN)") (class "Default")
      (node (ref "C27") (pin "+") (pinfunction "+_+") (pintype "passive"))
      (node (ref "IC5") (pin "5") (pinfunction "+IN_5") (pintype "input"))
      (node (ref "R10") (pin "1") (pinfunction "1_1") (pintype "passive"))
      (node (ref "R46") (pin "1") (pinfunction "1_1") (pintype "passive"))
      (node (ref "R50") (pin "2") (pinfunction "2_2") (pintype "passive"))
      (node (ref "R51") (pin "1") (pinfunction "1_1") (pintype "passive"))
      (node (ref "VR2") (pin "1") (pinfunction "1_1") (pintype "passive"))
    )
    (net (code "45") (name "Net-(IC5B--IN)") (class "Default")
      (node (ref "C28") (pin "2") (pinfunction "2_2") (pintype "passive"))
      (node (ref "IC5") (pin "6") (pinfunction "-IN_6") (pintype "input"))
      (node (ref "R52") (pin "2") (pinfunction "2_2") (pintype "passive"))
    )
    (net (code "46") (name "Net-(IC5B-OUT)") (class "Default")
      (node (ref "C28") (pin "1") (pinfunction "1_1") (pintype "passive"))
      (node (ref "IC5") (pin "7") (pinfunction "OUT_7") (pintype "output"))
      (node (ref "R49") (pin "2") (pinfunction "2_2") (pintype "passive"))
      (node (ref "VR2") (pin "3") (pinfunction "3_3") (pintype "passive"))
    )
    (net (code "47") (name "Net-(INPUT-T)") (class "Default")
      (node (ref "INPUT") (pin "TIP") (pinfunction "T_TIP") (pintype "passive"))
      (node (ref "R2") (pin "1") (pinfunction "1_1") (pintype "passive"))
    )
    (net (code "48") (name "Net-(LED-A)") (class "Default")
      (node (ref "D8") (pin "A") (pinfunction "A_A") (pintype "passive"))
      (node (ref "LED") (pin "ANODE") (pinfunction "A_ANODE") (pintype "passive"))
    )
    (net (code "49") (name "Net-(LED-C)") (class "Default")
      (node (ref "C33") (pin "1") (pinfunction "1_1") (pintype "passive"))
      (node (ref "LED") (pin "P$1") (pinfunction "C_P$1") (pintype "passive"))
      (node (ref "Q12") (pin "2") (pinfunction "C_2") (pintype "passive"))
      (node (ref "R12") (pin "1") (pinfunction "1_1") (pintype "passive"))
      (node (ref "R56") (pin "2") (pinfunction "2_2") (pintype "passive"))
      (node (ref "R59") (pin "1") (pinfunction "1_1") (pintype "passive"))
    )
    (net (code "50") (name "Net-(OUTPUT_A-TIP)") (class "Default")
      (node (ref "C7") (pin "-") (pinfunction "-_-") (pintype "passive"))
      (node (ref "OUTPUT_A") (pin "T") (pinfunction "TIP_T") (pintype "passive"))
      (node (ref "R5") (pin "2") (pinfunction "2_2") (pintype "passive"))
    )
    (net (code "51") (name "Net-(OUTPUT_B-TIP)") (class "Default")
      (node (ref "C8") (pin "-") (pinfunction "-_-") (pintype "passive"))
      (node (ref "OUTPUT_B") (pin "T") (pinfunction "TIP_T") (pintype "passive"))
      (node (ref "R9") (pin "2") (pinfunction "2_2") (pintype "passive"))
    )
    (net (code "52") (name "Net-(Q1-G)") (class "Default")
      (node (ref "C1") (pin "1") (pinfunction "1_1") (pintype "passive"))
      (node (ref "Q1") (pin "1") (pinfunction "G_1") (pintype "passive"))
      (node (ref "R4") (pin "2") (pinfunction "2_2") (pintype "passive"))
    )
    (net (code "53") (name "Net-(Q1-S)") (class "Default")
      (node (ref "C3") (pin "+") (pinfunction "+_+") (pintype "passive"))
      (node (ref "Q1") (pin "2") (pinfunction "S_2") (pintype "passive"))
      (node (ref "R3") (pin "2") (pinfunction "2_2") (pintype "passive"))
    )
    (net (code "54") (name "Net-(Q2-D)") (class "Default")
      (node (ref "Q2") (pin "3") (pinfunction "D_3") (pintype "passive"))
      (node (ref "R18") (pin "2") (pinfunction "2_2") (pintype "passive"))
    )
    (net (code "55") (name "Net-(Q2-G)") (class "Default")
      (node (ref "D4") (pin "A") (pinfunction "A_A") (pintype "passive"))
      (node (ref "D5") (pin "A") (pinfunction "A_A") (pintype "passive"))
      (node (ref "Q2") (pin "1") (pinfunction "G_1") (pintype "passive"))
    )
    (net (code "56") (name "Net-(Q3-D)") (class "Default")
      (node (ref "Q3") (pin "3") (pinfunction "D_3") (pintype "passive"))
      (node (ref "R15") (pin "2") (pinfunction "2_2") (pintype "passive"))
    )
    (net (code "57") (name "Net-(Q3-G)") (class "Default")
      (node (ref "D2") (pin "A") (pinfunction "A_A") (pintype "passive"))
      (node (ref "Q3") (pin "1") (pinfunction "G_1") (pintype "passive"))
    )
    (net (code "58") (name "Net-(Q4-D)") (class "Default")
      (node (ref "Q4") (pin "3") (pinfunction "D_3") (pintype "passive"))
      (node (ref "R36") (pin "2") (pinfunction "2_2") (pintype "passive"))
    )
    (net (code "59") (name "Net-(Q4-G)") (class "Default")
      (node (ref "D3") (pin "A") (pinfunction "A_A") (pintype "passive"))
      (node (ref "Q4") (pin "1") (pinfunction "G_1") (pintype "passive"))
    )
    (net (code "60") (name "Net-(Q5-D)") (class "Default")
      (node (ref "Q5") (pin "3") (pinfunction "D_3") (pintype "passive"))
      (node (ref "R28") (pin "2") (pinfunction "2_2") (pintype "passive"))
    )
    (net (code "61") (name "Net-(Q5-G)") (class "Default")
      (node (ref "D6") (pin "A") (pinfunction "A_A") (pintype "passive"))
      (node (ref "D7") (pin "A") (pinfunction "A_A") (pintype "passive"))
      (node (ref "Q5") (pin "1") (pinfunction "G_1") (pintype "passive"))
    )
    (net (code "62") (name "Net-(Q6-B)") (class "Default")
      (node (ref "C12") (pin "1") (pinfunction "1_1") (pintype "passive"))
      (node (ref "Q6") (pin "1") (pinfunction "B_1") (pintype "passive"))
      (node (ref "R24") (pin "2") (pinfunction "2_2") (pintype "passive"))
    )
    (net (code "63") (name "Net-(Q6-E)") (class "Default")
      (node (ref "C14") (pin "2") (pinfunction "2_2") (pintype "passive"))
      (node (ref "Q6") (pin "3") (pinfunction "E_3") (pintype "passive"))
      (node (ref "R25") (pin "2") (pinfunction "2_2") (pintype "passive"))
      (node (ref "R26") (pin "1") (pinfunction "1_1") (pintype "passive"))
    )
    (net (code "64") (name "Net-(Q7-B)") (class "Default")
      (node (ref "C15") (pin "+") (pinfunction "+_+") (pintype "passive"))
      (node (ref "Q7") (pin "1") (pinfunction "B_1") (pintype "passive"))
      (node (ref "R27") (pin "2") (pinfunction "2_2") (pintype "passive"))
    )
    (net (code "65") (name "Net-(Q8-B)") (class "Default")
      (node (ref "C22") (pin "1") (pinfunction "1_1") (pintype "passive"))
      (node (ref "Q8") (pin "1") (pinfunction "B_1") (pintype "passive"))
      (node (ref "R48") (pin "2") (pinfunction "2_2") (pintype "passive"))
    )
    (net (code "66") (name "Net-(Q8-E)") (class "Default")
      (node (ref "C21") (pin "2") (pinfunction "2_2") (pintype "passive"))
      (node (ref "C23") (pin "2") (pinfunction "2_2") (pintype "passive"))
      (node (ref "Q8") (pin "3") (pinfunction "E_3") (pintype "passive"))
      (node (ref "R37") (pin "2") (pinfunction "2_2") (pintype "passive"))
    )
    (net (code "67") (name "Net-(Q9-B)") (class "Default")
      (node (ref "Q9") (pin "1") (pinfunction "B_1") (pintype "passive"))
      (node (ref "R41") (pin "1") (pinfunction "1_1") (pintype "passive"))
    )
    (net (code "68") (name "Net-(Q9-C)") (class "Default")
      (node (ref "D11") (pin "C") (pinfunction "C_C") (pintype "passive"))
      (node (ref "Q9") (pin "2") (pinfunction "C_2") (pintype "passive"))
      (node (ref "R42") (pin "1") (pinfunction "1_1") (pintype "passive"))
    )
    (net (code "69") (name "Net-(Q10-B)") (class "Default")
      (node (ref "C26") (pin "1") (pinfunction "1_1") (pintype "passive"))
      (node (ref "Q10") (pin "1") (pinfunction "B_1") (pintype "passive"))
      (node (ref "R45") (pin "2") (pinfunction "2_2") (pintype "passive"))
    )
    (net (code "70") (name "Net-(Q10-E)") (class "Default")
      (node (ref "Q10") (pin "3") (pinfunction "E_3") (pintype "passive"))
      (node (ref "R44") (pin "2") (pinfunction "2_2") (pintype "passive"))
    )
    (net (code "71") (name "Net-(Q11-B)") (class "Default")
      (node (ref "C33") (pin "2") (pinfunction "2_2") (pintype "passive"))
      (node (ref "C34") (pin "1") (pinfunction "1_1") (pintype "passive"))
      (node (ref "Q11") (pin "1") (pinfunction "B_1") (pintype "passive"))
      (node (ref "R56") (pin "1") (pinfunction "1_1") (pintype "passive"))
      (node (ref "R57") (pin "2") (pinfunction "2_2") (pintype "passive"))
    )
    (net (code "72") (name "Net-(Q11-C)") (class "Default")
      (node (ref "C32") (pin "2") (pinfunction "2_2") (pintype "passive"))
      (node (ref "Q11") (pin "2") (pinfunction "C_2") (pintype "passive"))
      (node (ref "R55") (pin "1") (pinfunction "1_1") (pintype "passive"))
      (node (ref "R58") (pin "1") (pinfunction "1_1") (pintype "passive"))
      (node (ref "R61") (pin "1") (pinfunction "1_1") (pintype "passive"))
    )
    (net (code "73") (name "Net-(Q12-B)") (class "Default")
      (node (ref "C32") (pin "1") (pinfunction "1_1") (pintype "passive"))
      (node (ref "C35") (pin "1") (pinfunction "1_1") (pintype "passive"))
      (node (ref "Q12") (pin "1") (pinfunction "B_1") (pintype "passive"))
      (node (ref "R55") (pin "2") (pinfunction "2_2") (pintype "passive"))
      (node (ref "R60") (pin "2") (pinfunction "2_2") (pintype "passive"))
    )
    (net (code "74") (name "Net-(R10-Pad2)") (class "Default")
      (node (ref "R10") (pin "2") (pinfunction "2_2") (pintype "passive"))
      (node (ref "VR1") (pin "1") (pinfunction "1_1") (pintype "passive"))
    )
    (net (code "75") (name "Net-(R45-Pad1)") (class "Default")
      (node (ref "R45") (pin "1") (pinfunction "1_1") (pintype "passive"))
      (node (ref "VR2") (pin "2") (pinfunction "2_2") (pintype "passive"))
    )
    (net (code "76") (name "Net-(R52-Pad1)") (class "Default")
      (node (ref "R52") (pin "1") (pinfunction "1_1") (pintype "passive"))
      (node (ref "VR1") (pin "2") (pinfunction "2_2") (pintype "passive"))
    )
    (net (code "77") (name "Net-(R54-Pad2)") (class "Default")
      (node (ref "R54") (pin "2") (pinfunction "2_2") (pintype "passive"))
      (node (ref "VR3") (pin "1") (pinfunction "1_1") (pintype "passive"))
    )
    (net (code "78") (name "Net-(R64-Pad1)") (class "Default")
      (node (ref "R64") (pin "1") (pinfunction "1_1") (pintype "passive"))
      (node (ref "VR3") (pin "3") (pinfunction "3_3") (pintype "passive"))
    )
    (net (code "79") (name "Net-(SW1-O)") (class "Default")
      (node (ref "D2") (pin "C") (pinfunction "C_C") (pintype "passive"))
      (node (ref "D5") (pin "C") (pinfunction "C_C") (pintype "passive"))
      (node (ref "D7") (pin "C") (pinfunction "C_C") (pintype "passive"))
      (node (ref "R11") (pin "1") (pinfunction "1_1") (pintype "passive"))
      (node (ref "SW1") (pin "1") (pinfunction "O_1") (pintype "passive"))
    )
    (net (code "80") (name "Net-(SW1-P)") (class "Default")
      (node (ref "C9") (pin "1") (pinfunction "1_1") (pintype "passive"))
      (node (ref "R12") (pin "2") (pinfunction "2_2") (pintype "passive"))
      (node (ref "SW1") (pin "2") (pinfunction "P_2") (pintype "passive"))
    )
    (net (code "81") (name "Net-(SW2-S)") (class "Default")
      (node (ref "R63") (pin "1") (pinfunction "1_1") (pintype "passive"))
      (node (ref "SW2") (pin "2") (pinfunction "S_2") (pintype "passive"))
    )
    (net (code "82") (name "VA") (class "Default")
      (node (ref "IC3") (pin "5") (pinfunction "5_5") (pintype "bidirectional"))
      (node (ref "IC4") (pin "1") (pinfunction "P$1_1") (pintype "bidirectional"))
      (node (ref "Q10") (pin "2") (pinfunction "C_2") (pintype "passive"))
      (node (ref "Q7") (pin "3") (pinfunction "E_3") (pintype "passive"))
      (node (ref "R40") (pin "2") (pinfunction "2_2") (pintype "passive"))
      (node (ref "R42") (pin "2") (pinfunction "2_2") (pintype "passive"))
      (node (ref "R46") (pin "2") (pinfunction "2_2") (pintype "passive"))
    )
    (net (code "83") (name "unconnected-(IC4-P$6-Pad6)") (class "Default")
      (node (ref "IC4") (pin "6") (pinfunction "P$6_6") (pintype "bidirectional"))
    )
    (net (code "84") (name "unconnected-(SW1-S-Pad3)") (class "Default")
      (node (ref "SW1") (pin "3") (pinfunction "S_3") (pintype "passive"))
    )
  )
)
